# RTC.net
KiCad netlist of a schematic drawn in Altium Designer
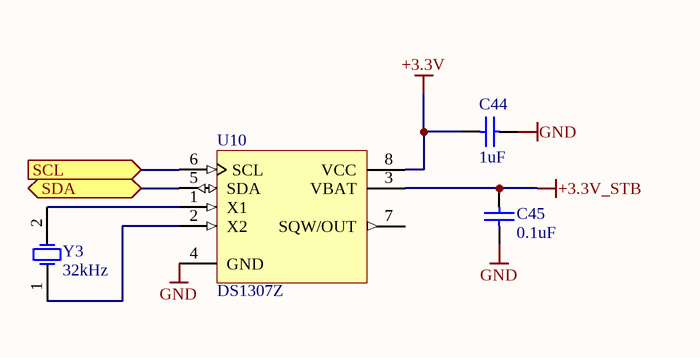
[diagram p0: RTC.SchDoc]

(export (version "E")
  (design (tool "Eeschema 10.0.6"))
  (components
    (comp (ref "C44")
      (value "1uF")
      (footprint "1608[0603]")
      (description "Ceramic Chip Capacitor - Standard")
      (fields (field (name "PUBLISHER") "Altium Limited"))
      (libsource (lib "ResAndCaps") (part "C0603"))
    )
    (comp (ref "C45")
      (value "0.1uF")
      (footprint "1608[0603]")
      (description "Ceramic Chip Capacitor - Standard")
      (fields (field (name "PUBLISHER") "Altium Limited"))
      (libsource (lib "ResAndCaps") (part "C0603"))
    )
    (comp (ref "U10")
      (value "DS1307Z")
      (footprint "SOIC8N_N")
      (description "64 X 8 Serial Real-Time Clock")
      (fields (field (name "PUBLISHER") "Altium Limited"))
      (libsource (lib "Dallas Peripheral Real Time Clock") (part "DS1307Z"))
    )
    (comp (ref "Y3")
      (value "32kHz")
      (footprint "R38")
      (description "Crystal Oscillator")
      (fields (field (name "PUBLISHER") "Altium Limited"))
      (libsource (lib "Miscellaneous Devices") (part "XTAL"))
    )
  )
  (nets
    (net (code "1") (name "+3.3V") (class "Default")
      (node (ref "C44") (pin "1") (pinfunction "1_1") (pintype "passive"))
      (node (ref "U10") (pin "8") (pinfunction "VCC_8") (pintype "power_in"))
    )
    (net (code "2") (name "+3.3V_STB") (class "Default")
      (node (ref "C45") (pin "2") (pinfunction "2_2") (pintype "passive"))
      (node (ref "U10") (pin "3") (pinfunction "VBAT_3") (pintype "power_in"))
    )
    (net (code "3") (name "/SCL") (class "Default")
      (node (ref "U10") (pin "6") (pinfunction "SCL_6") (pintype "input"))
    )
    (net (code "4") (name "/SDA") (class "Default")
      (node (ref "U10") (pin "5") (pinfunction "SDA_5") (pintype "bidirectional"))
    )
    (net (code "5") (name "GND") (class "Default")
      (node (ref "C44") (pin "2") (pinfunction "2_2") (pintype "passive"))
      (node (ref "C45") (pin "1") (pinfunction "1_1") (pintype "passive"))
      (node (ref "U10") (pin "4") (pinfunction "GND_4") (pintype "power_in"))
    )
    (net (code "6") (name "Net-(U10-X1)") (class "Default")
      (node (ref "U10") (pin "1") (pinfunction "X1_1") (pintype "input"))
      (node (ref "Y3") (pin "2") (pinfunction "OSC2_2") (pintype "passive"))
    )
    (net (code "7") (name "Net-(U10-X2)") (class "Default")
      (node (ref "U10") (pin "2") (pinfunction "X2_2") (pintype "input"))
      (node (ref "Y3") (pin "1") (pinfunction "OSC1_1") (pintype "passive"))
    )
    (net (code "8") (name "unconnected-(U10-SQW{slash}OUT-Pad7)") (class "Default")
      (node (ref "U10") (pin "7") (pinfunction "SQW/OUT_7") (pintype "output"))
    )
  )
)
